# TinyEncoderReader.net
KiCad netlist of a schematic drawn in EAGLE
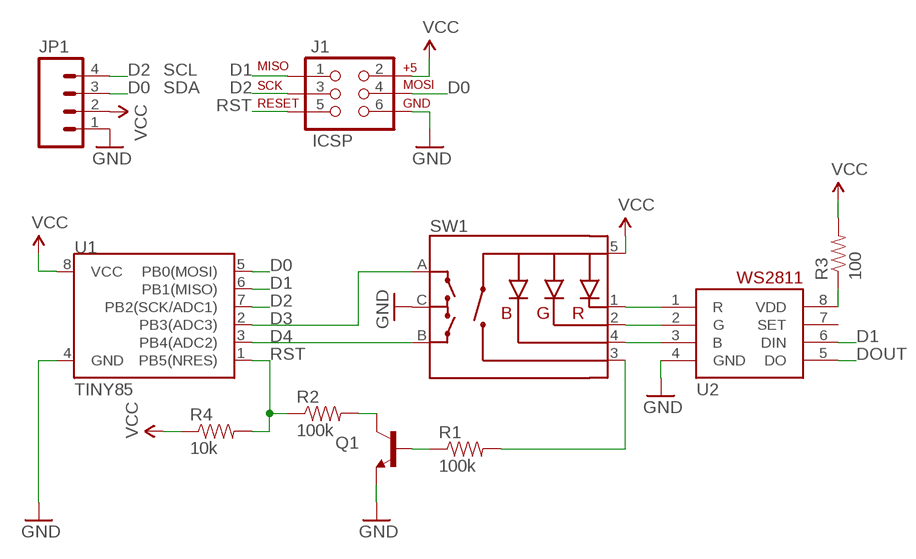
[diagram p0: schematic, sheet 1]

(export (version "E")
  (design (tool "Eeschema 10.0.6"))
  (components
    (comp (ref "J1")
      (value "ICSP")
      (footprint "eagle-import:2X3-NS")
      (libsource (lib "eagle-import") (part "AVR_SPI_PRG_6LABELED"))
    )
    (comp (ref "JP1")
      (value "M04PTH")
      (footprint "eagle-import:1X04")
      (libsource (lib "eagle-import") (part "M04PTH"))
    )
    (comp (ref "Q1")
      (value "TRANSISTOR_NPNTO-92-AMMO")
      (footprint "eagle-import:TO-92-AMMO")
      (libsource (lib "eagle-import") (part "TRANSISTOR_NPNTO-92-AMMO"))
    )
    (comp (ref "R1")
      (value "100k")
      (footprint "eagle-import:AXIAL-0.3")
      (libsource (lib "eagle-import") (part "RESISTORAXIAL-0.3"))
    )
    (comp (ref "R2")
      (value "100k")
      (footprint "eagle-import:AXIAL-0.3")
      (libsource (lib "eagle-import") (part "RESISTORAXIAL-0.3"))
    )
    (comp (ref "R3")
      (value "100")
      (footprint "eagle-import:AXIAL-0.3")
      (libsource (lib "eagle-import") (part "RESISTORAXIAL-0.3"))
    )
    (comp (ref "R4")
      (value "10k")
      (footprint "eagle-import:AXIAL-0.3")
      (libsource (lib "eagle-import") (part "RESISTORAXIAL-0.3"))
    )
    (comp (ref "SW1")
      (value "ENCODER_RGB_CA")
      (footprint "eagle-import:ENCODER_LED_3")
      (libsource (lib "eagle-import") (part "ENCODER_RGB_CA"))
    )
    (comp (ref "U1")
      (value "TINY85")
      (footprint "eagle-import:DIP08")
      (libsource (lib "eagle-import") (part "ATTINY45TINY85-20-DIP"))
    )
    (comp (ref "U2")
      (value "WS2811")
      (footprint "eagle-import:SO08-SKINNYPADS")
      (libsource (lib "eagle-import") (part "WS2811-SOP8"))
    )
  )
  (nets
    (net (code "1") (name "/D0") (class "Default")
      (node (ref "J1") (pin "4") (pinfunction "MOSI_4") (pintype "passive"))
      (node (ref "JP1") (pin "3") (pinfunction "3_3") (pintype "passive"))
      (node (ref "U1") (pin "5") (pinfunction "PB0(MOSI)_5") (pintype "bidirectional"))
    )
    (net (code "2") (name "/D1") (class "Default")
      (node (ref "J1") (pin "1") (pinfunction "MISO_1") (pintype "passive"))
      (node (ref "U1") (pin "6") (pinfunction "PB1(MISO)_6") (pintype "bidirectional"))
      (node (ref "U2") (pin "6") (pinfunction "DIN_6") (pintype "input"))
    )
    (net (code "3") (name "/D2") (class "Default")
      (node (ref "J1") (pin "3") (pinfunction "SCK_3") (pintype "passive"))
      (node (ref "JP1") (pin "4") (pinfunction "4_4") (pintype "passive"))
      (node (ref "U1") (pin "7") (pinfunction "PB2(SCK/ADC1)_7") (pintype "bidirectional"))
    )
    (net (code "4") (name "/D3") (class "Default")
      (node (ref "SW1") (pin "A") (pinfunction "A_A") (pintype "bidirectional"))
      (node (ref "U1") (pin "2") (pinfunction "PB3(ADC3)_2") (pintype "bidirectional"))
    )
    (net (code "5") (name "/D4") (class "Default")
      (node (ref "SW1") (pin "B") (pinfunction "B_B") (pintype "bidirectional"))
      (node (ref "U1") (pin "3") (pinfunction "PB4(ADC2)_3") (pintype "bidirectional"))
    )
    (net (code "6") (name "/DOUT") (class "Default")
      (node (ref "U2") (pin "5") (pinfunction "DO_5") (pintype "output"))
    )
    (net (code "7") (name "/RST") (class "Default")
      (node (ref "J1") (pin "5") (pinfunction "RST_5") (pintype "passive"))
      (node (ref "R2") (pin "P$1") (pinfunction "1_P$1") (pintype "passive"))
      (node (ref "R4") (pin "P$2") (pinfunction "2_P$2") (pintype "passive"))
      (node (ref "U1") (pin "1") (pinfunction "PB5(NRES)_1") (pintype "bidirectional"))
    )
    (net (code "8") (name "GND") (class "Default")
      (node (ref "J1") (pin "6") (pinfunction "GND_6") (pintype "passive"))
      (node (ref "JP1") (pin "1") (pinfunction "1_1") (pintype "passive"))
      (node (ref "Q1") (pin "1") (pinfunction "E_1") (pintype "passive"))
      (node (ref "SW1") (pin "C") (pinfunction "C_C") (pintype "bidirectional"))
      (node (ref "U1") (pin "4") (pinfunction "GND_4") (pintype "bidirectional"))
      (node (ref "U2") (pin "4") (pinfunction "GND_4") (pintype "power_in"))
    )
    (net (code "9") (name "Net-(Q1-B)") (class "Default")
      (node (ref "Q1") (pin "2") (pinfunction "B_2") (pintype "passive"))
      (node (ref "R1") (pin "P$1") (pinfunction "1_P$1") (pintype "passive"))
    )
    (net (code "10") (name "Net-(Q1-C)") (class "Default")
      (node (ref "Q1") (pin "3") (pinfunction "C_3") (pintype "passive"))
      (node (ref "R2") (pin "P$2") (pinfunction "2_P$2") (pintype "passive"))
    )
    (net (code "11") (name "Net-(R1-2)") (class "Default")
      (node (ref "R1") (pin "P$2") (pinfunction "2_P$2") (pintype "passive"))
      (node (ref "SW1") (pin "3") (pinfunction "SW_3") (pintype "passive"))
    )
    (net (code "12") (name "Net-(R3-1)") (class "Default")
      (node (ref "R3") (pin "P$1") (pinfunction "1_P$1") (pintype "passive"))
      (node (ref "U2") (pin "8") (pinfunction "VDD_8") (pintype "power_in"))
    )
    (net (code "13") (name "Net-(SW1--B)") (class "Default")
      (node (ref "SW1") (pin "4") (pinfunction "-B_4") (pintype "passive"))
      (node (ref "U2") (pin "3") (pinfunction "B_3") (pintype "open_collector"))
    )
    (net (code "14") (name "Net-(SW1--G)") (class "Default")
      (node (ref "SW1") (pin "2") (pinfunction "-G_2") (pintype "passive"))
      (node (ref "U2") (pin "2") (pinfunction "G_2") (pintype "open_collector"))
    )
    (net (code "15") (name "Net-(SW1--R)") (class "Default")
      (node (ref "SW1") (pin "1") (pinfunction "-R_1") (pintype "passive"))
      (node (ref "U2") (pin "1") (pinfunction "R_1") (pintype "open_collector"))
    )
    (net (code "16") (name "VCC") (class "Default")
      (node (ref "J1") (pin "2") (pinfunction "V+_2") (pintype "passive"))
      (node (ref "JP1") (pin "2") (pinfunction "2_2") (pintype "passive"))
      (node (ref "R3") (pin "P$2") (pinfunction "2_P$2") (pintype "passive"))
      (node (ref "R4") (pin "P$1") (pinfunction "1_P$1") (pintype "passive"))
      (node (ref "SW1") (pin "5") (pinfunction "+_5") (pintype "passive"))
      (node (ref "U1") (pin "8") (pinfunction "VCC_8") (pintype "bidirectional"))
    )
    (net (code "17") (name "unconnected-(U2-SET-Pad7)") (class "Default")
      (node (ref "U2") (pin "7") (pinfunction "SET_7") (pintype "input"))
    )
  )
)
